# Power_Supply.net
KiCad netlist of a schematic drawn in Altium Designer
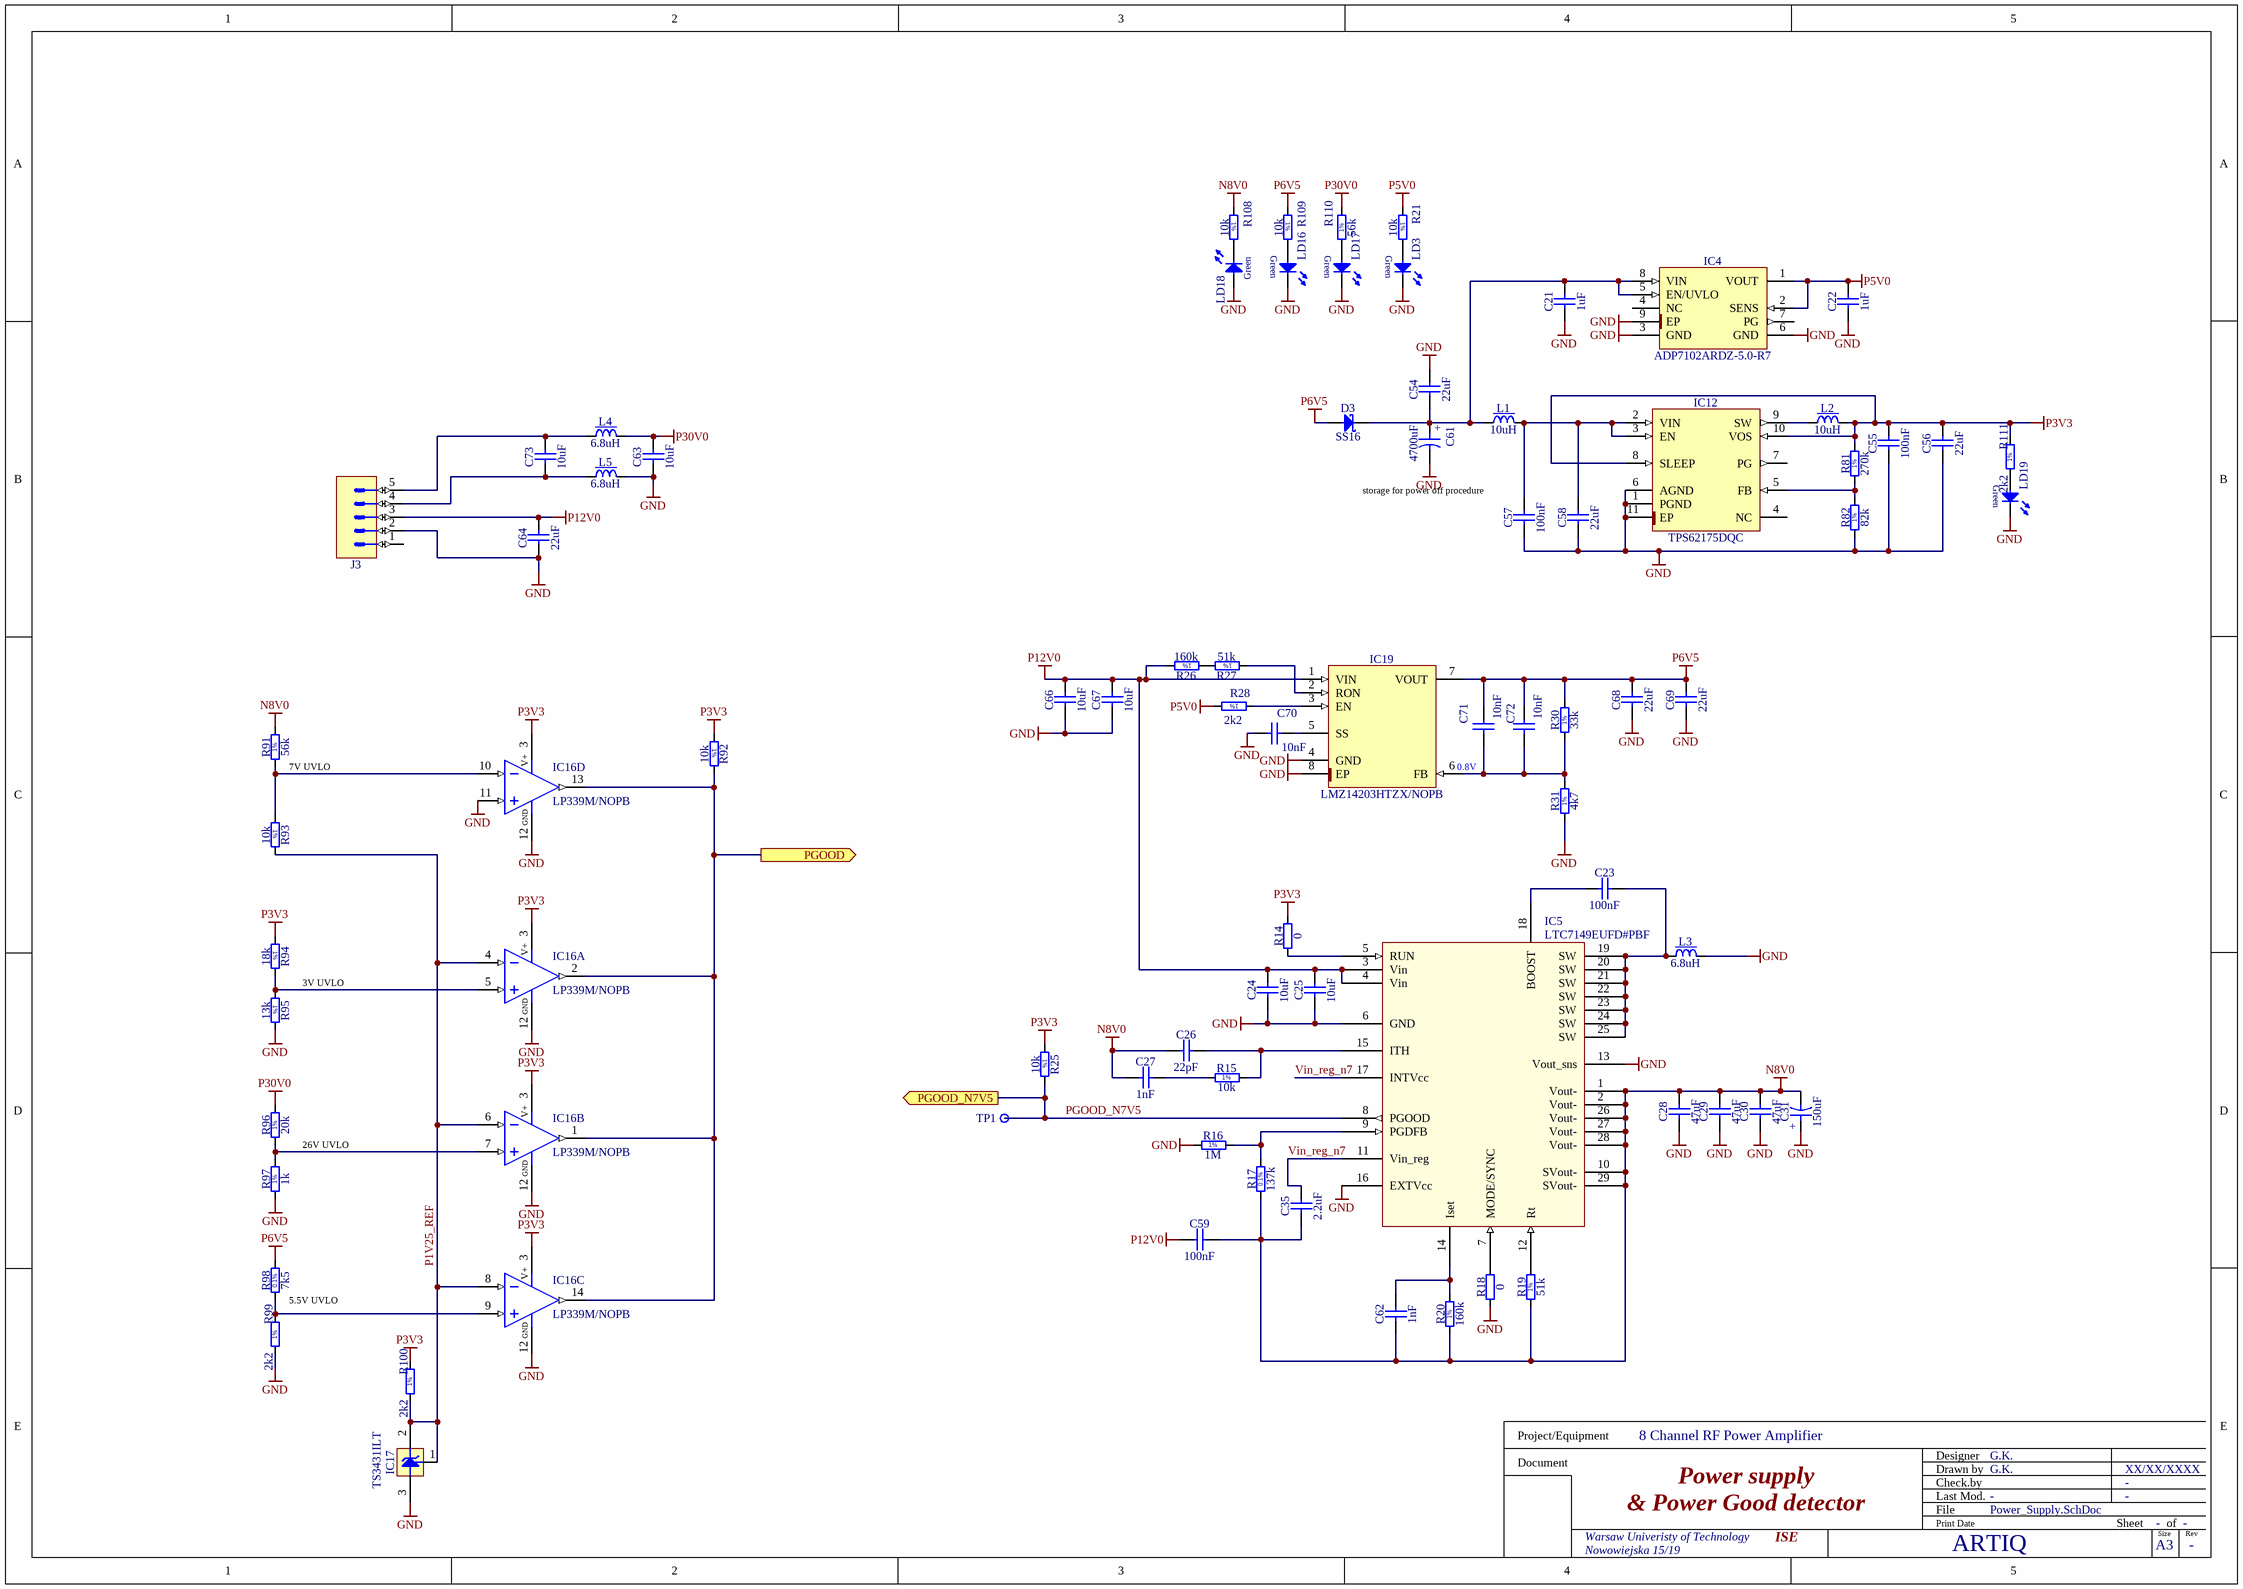
[diagram p0: Power_Supply.SchDoc]

(export (version "E")
  (design (tool "Eeschema 10.0.6"))
  (components
    (comp (ref "C21")
      (value "1uF")
      (footprint "CAPC2012X140N")
      (description "Non-polarised capacitor")
      (fields
        (field (name "PART NUMBER") "CC0805_1UF_35V_20%_X7R")
        (field (name "VOLTAGE") "35V")
        (field (name "AUTHOR") "CERN DEM JLC")
      )
      (libsource (lib "Capacitors") (part "Capacitor - non polarized"))
    )
    (comp (ref "C22")
      (value "1uF")
      (footprint "CAPC2012X140N")
      (description "Non-polarised capacitor")
      (fields
        (field (name "PART NUMBER") "CC0805_1UF_35V_20%_X7R")
        (field (name "VOLTAGE") "35V")
        (field (name "AUTHOR") "CERN DEM JLC")
      )
      (libsource (lib "Capacitors") (part "Capacitor - non polarized"))
    )
    (comp (ref "C23")
      (value "100nF")
      (footprint "CAPC1005X55N")
      (description "Non-polarised capacitor")
      (fields
        (field (name "PART NUMBER") "CC0402_100NF_16V_10%_X7R")
        (field (name "VOLTAGE") "16V")
        (field (name "AUTHOR") "CERN DEM JLC")
      )
      (libsource (lib "Capacitors") (part "Capacitor - non polarized"))
    )
    (comp (ref "C24")
      (value "10uF")
      (footprint "CAPC3216X190N")
      (description "Non-polarised capacitor")
      (fields
        (field (name "PART NUMBER") "CC1206_10UF_50V_10%_X5R_TDK_CGA5L3X5R1H106K160AB")
        (field (name "VOLTAGE") "50V")
        (field (name "AUTHOR") "CERN DEM BC")
      )
      (libsource (lib "Capacitors") (part "Capacitor - non polarized"))
    )
    (comp (ref "C25")
      (value "10uF")
      (footprint "CAPC3216X190N")
      (description "Non-polarised capacitor")
      (fields
        (field (name "PART NUMBER") "CC1206_10UF_50V_10%_X5R_TDK_CGA5L3X5R1H106K160AB")
        (field (name "VOLTAGE") "50V")
        (field (name "AUTHOR") "CERN DEM BC")
      )
      (libsource (lib "Capacitors") (part "Capacitor - non polarized"))
    )
    (comp (ref "C26")
      (value "22pF")
      (footprint "CAPC1005X55N")
      (description "Non-polarised capacitor")
      (fields
        (field (name "PART NUMBER") "CC0402_22PF_50V_5%_C0G")
        (field (name "VOLTAGE") "50V")
        (field (name "AUTHOR") "CERN DEM JLC")
      )
      (libsource (lib "Capacitors") (part "Capacitor - non polarized"))
    )
    (comp (ref "C27")
      (value "1nF")
      (footprint "CAPC1005X55N")
      (description "Non-polarised capacitor")
      (fields
        (field (name "PART NUMBER") "CC0402_1NF_50V_10%_X7R")
        (field (name "VOLTAGE") "50V")
        (field (name "AUTHOR") "CERN DEM JLC")
      )
      (libsource (lib "Capacitors") (part "Capacitor - non polarized"))
    )
    (comp (ref "C28")
      (value "47uF")
      (footprint "CAPC3216X180N")
      (description "Non-polarised capacitor")
      (fields
        (field (name "PART NUMBER") "CC1206_47UF_25V_20%_X5R")
        (field (name "VOLTAGE") "25V")
        (field (name "AUTHOR") "CERN DEM JLC")
      )
      (libsource (lib "Capacitors") (part "Capacitor - non polarized"))
    )
    (comp (ref "C29")
      (value "47uF")
      (footprint "CAPC3216X180N")
      (description "Non-polarised capacitor")
      (fields
        (field (name "PART NUMBER") "CC1206_47UF_25V_20%_X5R")
        (field (name "VOLTAGE") "25V")
        (field (name "AUTHOR") "CERN DEM JLC")
      )
      (libsource (lib "Capacitors") (part "Capacitor - non polarized"))
    )
    (comp (ref "C30")
      (value "47uF")
      (footprint "CAPC3216X180N")
      (description "Non-polarised capacitor")
      (fields
        (field (name "PART NUMBER") "CC1206_47UF_25V_20%_X5R")
        (field (name "VOLTAGE") "25V")
        (field (name "AUTHOR") "CERN DEM JLC")
      )
      (libsource (lib "Capacitors") (part "Capacitor - non polarized"))
    )
    (comp (ref "C31")
      (value "150uF")
      (footprint "CAPMP7343X310N")
      (description "Polarised capacitor")
      (fields
        (field (name "PART NUMBER") "CTE7343-31_150UF_16V_10%_LESR0100")
        (field (name "VOLTAGE") "16V")
        (field (name "AUTHOR") "CERN DEM JLC")
      )
      (libsource (lib "Capacitors") (part "Capacitor - polarized"))
    )
    (comp (ref "C35")
      (value "2.2uF")
      (footprint "CAPC1608X87N")
      (description "Non-polarised capacitor")
      (fields
        (field (name "PART NUMBER") "CC0603_2.2UF_16V_10%_X5R")
        (field (name "VOLTAGE") "16V")
        (field (name "AUTHOR") "CERN DEM JLC")
      )
      (libsource (lib "Capacitors") (part "Capacitor - non polarized"))
    )
    (comp (ref "C54")
      (value "22uF")
      (footprint "CAPC2012X135N")
      (description "Non-polarised capacitor")
      (fields
        (field (name "PART NUMBER") "CC0805_22UF_16V_10%_X5R")
        (field (name "VOLTAGE") "16V")
        (field (name "AUTHOR") "CERN DEM JLC")
      )
      (libsource (lib "Capacitors") (part "Capacitor - non polarized"))
    )
    (comp (ref "C55")
      (value "100nF")
      (footprint "CAPC1005X55N")
      (description "Non-polarised capacitor")
      (fields
        (field (name "PART NUMBER") "CC0402_100NF_16V_10%_X5R")
        (field (name "VOLTAGE") "16V")
        (field (name "AUTHOR") "CERN DEM JLC")
      )
      (libsource (lib "Capacitors") (part "Capacitor - non polarized"))
    )
    (comp (ref "C56")
      (value "22uF")
      (footprint "CAPC2012X135N")
      (description "Non-polarised capacitor")
      (fields
        (field (name "PART NUMBER") "CC0805_22UF_16V_10%_X5R")
        (field (name "VOLTAGE") "16V")
        (field (name "AUTHOR") "CERN DEM JLC")
      )
      (libsource (lib "Capacitors") (part "Capacitor - non polarized"))
    )
    (comp (ref "C57")
      (value "100nF")
      (footprint "CAPC1005X55N")
      (description "Non-polarised capacitor")
      (fields
        (field (name "PART NUMBER") "CC0402_100NF_16V_10%_X5R")
        (field (name "VOLTAGE") "16V")
        (field (name "AUTHOR") "CERN DEM JLC")
      )
      (libsource (lib "Capacitors") (part "Capacitor - non polarized"))
    )
    (comp (ref "C58")
      (value "22uF")
      (footprint "CAPC2012X135N")
      (description "Non-polarised capacitor")
      (fields
        (field (name "PART NUMBER") "CC0805_22UF_16V_10%_X5R")
        (field (name "VOLTAGE") "16V")
        (field (name "AUTHOR") "CERN DEM JLC")
      )
      (libsource (lib "Capacitors") (part "Capacitor - non polarized"))
    )
    (comp (ref "C59")
      (value "100nF")
      (footprint "CAPC1608X87N")
      (description "Non-polarised capacitor")
      (fields
        (field (name "PART NUMBER") "CC0603_100NF_50V_10%_X5R")
        (field (name "VOLTAGE") "50V")
        (field (name "AUTHOR") "CERN DEM MR")
      )
      (libsource (lib "Capacitors") (part "Capacitor - non polarized"))
    )
    (comp (ref "C61")
      (value "4700uF")
      (footprint "CAPAE1900X1680N")
      (description "Polarised capacitor")
      (fields
        (field (name "PART NUMBER") "CAE1900-1680_4700UF_16V_20%")
        (field (name "VOLTAGE") "16V")
        (field (name "AUTHOR") "CERN DEM JLC")
      )
      (libsource (lib "Capacitors") (part "Capacitor - polarized"))
    )
    (comp (ref "C62")
      (value "1nF")
      (footprint "CAPC1005X55N")
      (description "Non-polarised capacitor")
      (fields
        (field (name "PART NUMBER") "CC0402_1NF_50V_10%_X7R")
        (field (name "VOLTAGE") "50V")
        (field (name "AUTHOR") "CERN DEM JLC")
      )
      (libsource (lib "Capacitors") (part "Capacitor - non polarized"))
    )
    (comp (ref "C63")
      (value "10uF")
      (footprint "CAPC3216X190N")
      (description "Non-polarised capacitor")
      (fields
        (field (name "PART NUMBER") "CC1206_10UF_50V_10%_X5R_TDK_CGA5L3X5R1H106K160AB")
        (field (name "VOLTAGE") "50V")
        (field (name "AUTHOR") "CERN DEM BC")
      )
      (libsource (lib "Capacitors") (part "Capacitor - non polarized"))
    )
    (comp (ref "C64")
      (value "22uF")
      (footprint "CAPC2012X135N")
      (description "Non-polarised capacitor")
      (fields
        (field (name "PART NUMBER") "CC0805_22UF_16V_10%_X5R")
        (field (name "VOLTAGE") "16V")
        (field (name "AUTHOR") "CERN DEM JLC")
      )
      (libsource (lib "Capacitors") (part "Capacitor - non polarized"))
    )
    (comp (ref "C66")
      (value "10uF")
      (footprint "CAPC3216X190N")
      (description "Non-polarised capacitor")
      (fields
        (field (name "PART NUMBER") "CC1206_10UF_50V_10%_X5R_TDK_CGA5L3X5R1H106K160AB")
        (field (name "VOLTAGE") "50V")
        (field (name "AUTHOR") "CERN DEM BC")
      )
      (libsource (lib "Capacitors") (part "Capacitor - non polarized"))
    )
    (comp (ref "C67")
      (value "10uF")
      (footprint "CAPC3216X190N")
      (description "Non-polarised capacitor")
      (fields
        (field (name "PART NUMBER") "CC1206_10UF_50V_10%_X5R_TDK_CGA5L3X5R1H106K160AB")
        (field (name "VOLTAGE") "50V")
        (field (name "AUTHOR") "CERN DEM BC")
      )
      (libsource (lib "Capacitors") (part "Capacitor - non polarized"))
    )
    (comp (ref "C68")
      (value "22uF")
      (footprint "CAPC2012X135N")
      (description "Non-polarised capacitor")
      (fields
        (field (name "PART NUMBER") "CC0805_22UF_16V_10%_X5R")
        (field (name "VOLTAGE") "16V")
        (field (name "AUTHOR") "CERN DEM JLC")
      )
      (libsource (lib "Capacitors") (part "Capacitor - non polarized"))
    )
    (comp (ref "C69")
      (value "22uF")
      (footprint "CAPC2012X135N")
      (description "Non-polarised capacitor")
      (fields
        (field (name "PART NUMBER") "CC0805_22UF_16V_10%_X5R")
        (field (name "VOLTAGE") "16V")
        (field (name "AUTHOR") "CERN DEM JLC")
      )
      (libsource (lib "Capacitors") (part "Capacitor - non polarized"))
    )
    (comp (ref "C70")
      (value "10nF")
      (footprint "CAPC1608X87N")
      (description "Non-polarised capacitor")
      (fields
        (field (name "PART NUMBER") "CC0603_10NF_50V_5%_C0G")
        (field (name "VOLTAGE") "50V")
        (field (name "AUTHOR") "CERN DEM JLC")
      )
      (libsource (lib "Capacitors") (part "Capacitor - non polarized"))
    )
    (comp (ref "C71")
      (value "10nF")
      (footprint "CAPC1608X87N")
      (description "Non-polarised capacitor")
      (fields
        (field (name "PART NUMBER") "CC0603_10NF_50V_5%_C0G")
        (field (name "VOLTAGE") "50V")
        (field (name "AUTHOR") "CERN DEM JLC")
      )
      (libsource (lib "Capacitors") (part "Capacitor - non polarized"))
    )
    (comp (ref "C72")
      (value "10nF")
      (footprint "CAPC1608X87N")
      (description "Non-polarised capacitor")
      (fields
        (field (name "PART NUMBER") "CC0603_10NF_50V_5%_C0G")
        (field (name "VOLTAGE") "50V")
        (field (name "AUTHOR") "CERN DEM JLC")
      )
      (libsource (lib "Capacitors") (part "Capacitor - non polarized"))
    )
    (comp (ref "C73")
      (value "10uF")
      (footprint "CAPC3216X190N")
      (description "Non-polarised capacitor")
      (fields
        (field (name "PART NUMBER") "CC1206_10UF_50V_10%_X5R_TDK_CGA5L3X5R1H106K160AB")
        (field (name "VOLTAGE") "50V")
        (field (name "AUTHOR") "CERN DEM BC")
      )
      (libsource (lib "Capacitors") (part "Capacitor - non polarized"))
    )
    (comp (ref "D3")
      (value "SS16")
      (footprint "DIOM5127X229N")
      (description "Schottky Diode")
      (fields
        (field (name "VOLTAGE") "60V")
        (field (name "POWER") "1A")
        (field (name "AUTHOR") "CERN DEM JLC")
      )
      (libsource (lib "ICs And Semiconductors") (part "Diode Schottky"))
    )
    (comp (ref "IC4")
      (value "ADP7102ARDZ-5.0-R7")
      (footprint "SOIC127P600X175-9N-R241X309")
      (description "300 mA, Low Noise, CMOS LDO Linear Regulator")
      (fields (field (name "MANUFACTURER") "ANALOG DEVICES") (field (name "AUTHOR") "CERN DEM JLC"))
      (libsource (lib "ICs And Semiconductors") (part "ADP7102ARDZ-X.X-R7"))
    )
    (comp (ref "IC5")
      (value "LTC7149EUFD#PBF")
      (footprint "QFN50P400X500X80_HS-29N")
      (description "LTC7149 - 60V, 4A Synchronous Step-Down Regulator for Inverting Outputs")
      (fields (field (name "MANUFACTURER") "Linear technology"))
      (libsource (lib "misc") (part "LTC7149EUFD#PBF"))
    )
    (comp (ref "IC12")
      (value "TPS62175DQC")
      (footprint "SON50P200X300X80-11N-R94X250")
      (description "4.75-28VDC to 1-6VDC, 500mA Step-Down Converter With Sleep Mode")
      (fields (field (name "MANUFACTURER") "TEXAS INSTRUMENTS") (field (name "AUTHOR") "CERN DEM JMW"))
      (libsource (lib "ICs And Semiconductors") (part "TPS62175"))
    )
    (comp (ref "IC16")
      (value "LP339M/NOPB")
      (footprint "SOIC127P600X175-14N")
      (description "Quad Operational Amplifier")
      (fields (field (name "MANUFACTURER") "TEXAS INSTRUMENTS") (field (name "AUTHOR") "CERN DEM MR"))
      (libsource (lib "ICs And Semiconductors") (part "Operational Amplifier x4 Type5"))
    )
    (comp (ref "IC17")
      (value "TS3431ILT")
      (footprint "SOT95P237X112-3N")
      (description "Precision Reference 1=Adj 2=Cathode 3=Anode")
      (fields (field (name "MANUFACTURER") "ST MICROELECTRONICS") (field (name "AUTHOR") "CERN DEM JLC"))
      (libsource (lib "ICs And Semiconductors") (part "VREF 1ADJ-2C-3A"))
    )
    (comp (ref "IC19")
      (value "LMZ14203HTZX/NOPB")
      (footprint "TEXAS_TO-PMOD (NDW)")
      (description "3A SIMPLE SWITCHER® Power Module with 42V Maximum Input Voltage")
      (fields (field (name "MANUFACTURER") "TEXAS INSTRUMENTS") (field (name "AUTHOR") "GK"))
      (libsource (lib "LIBRARY_SCH") (part "PM_LMZ14203"))
    )
    (comp (ref "J3")
      (value "~")
      (footprint "PHOENIX_1755765")
      (description "Connector 5 Male")
      (fields
        (field (name "PART NUMBER") "PHOENIX_1755765")
        (field (name "MANUFACTURER") "PHOENIX CONTACT")
        (field (name "AUTHOR") "CERN DEM JLC")
      )
      (libsource (lib "Connectors") (part "Connector 5 Male"))
    )
    (comp (ref "L1")
      (value "10uH")
      (footprint "IND_MURATA-PS_8400")
      (description "Inductor With Core")
      (fields
        (field (name "PART NUMBER") "IND_10UH_10%_MURATA-PS_8400")
        (field (name "POWER") "950mA")
        (field (name "AUTHOR") "CERN DEM JLC")
      )
      (libsource (lib "Inductors & Transformers") (part "Inductor With Magnetic core"))
    )
    (comp (ref "L2")
      (value "10uH")
      (footprint "IND_MURATA-PS_8400")
      (description "Inductor With Core")
      (fields
        (field (name "PART NUMBER") "IND_10UH_10%_MURATA-PS_8400")
        (field (name "POWER") "950mA")
        (field (name "AUTHOR") "CERN DEM JLC")
      )
      (libsource (lib "Inductors & Transformers") (part "Inductor With Magnetic core"))
    )
    (comp (ref "L3")
      (value "6.8uH")
      (footprint "INDM6965X300N")
      (description "Inductor With Core")
      (fields
        (field (name "PART NUMBER") "IND2525_1.5UH_20%_VISHAY_IHLP-2525CZ")
        (field (name "POWER") "9A")
        (field (name "AUTHOR") "CERN DEM JLC")
      )
      (libsource (lib "Inductors & Transformers") (part "Inductor With Magnetic core"))
    )
    (comp (ref "L4")
      (value "6.8uH")
      (footprint "INDM6965X300N")
      (description "Inductor With Core")
      (fields
        (field (name "PART NUMBER") "IND2525_1.5UH_20%_VISHAY_IHLP-2525CZ")
        (field (name "POWER") "9A")
        (field (name "AUTHOR") "CERN DEM JLC")
      )
      (libsource (lib "Inductors & Transformers") (part "Inductor With Magnetic core"))
    )
    (comp (ref "L5")
      (value "6.8uH")
      (footprint "INDM6965X300N")
      (description "Inductor With Core")
      (fields
        (field (name "PART NUMBER") "IND2525_1.5UH_20%_VISHAY_IHLP-2525CZ")
        (field (name "POWER") "9A")
        (field (name "AUTHOR") "CERN DEM JLC")
      )
      (libsource (lib "Inductors & Transformers") (part "Inductor With Magnetic core"))
    )
    (comp (ref "LD3")
      (value "Green")
      (footprint "LED_KINGBRIGHT_KPH-1608CGCK")
      (description "LED Green 1C 2A")
      (fields
        (field (name "PART NUMBER") "LED_KINGBRIGHT_KPH-1608CGCK")
        (field (name "MANUFACTURER") "KINGBRIGHT")
        (field (name "AUTHOR") "CERN DEM JLC")
      )
      (libsource (lib "ICs And Semiconductors") (part "LED Green 1C 2A"))
    )
    (comp (ref "LD16")
      (value "Green")
      (footprint "LED_KINGBRIGHT_KPH-1608CGCK")
      (description "LED Green 1C 2A")
      (fields
        (field (name "PART NUMBER") "LED_KINGBRIGHT_KPH-1608CGCK")
        (field (name "MANUFACTURER") "KINGBRIGHT")
        (field (name "AUTHOR") "CERN DEM JLC")
      )
      (libsource (lib "ICs And Semiconductors") (part "LED Green 1C 2A"))
    )
    (comp (ref "LD17")
      (value "Green")
      (footprint "LED_KINGBRIGHT_KPH-1608CGCK")
      (description "LED Green 1C 2A")
      (fields
        (field (name "PART NUMBER") "LED_KINGBRIGHT_KPH-1608CGCK")
        (field (name "MANUFACTURER") "KINGBRIGHT")
        (field (name "AUTHOR") "CERN DEM JLC")
      )
      (libsource (lib "ICs And Semiconductors") (part "LED Green 1C 2A"))
    )
    (comp (ref "LD18")
      (value "Green")
      (footprint "LED_KINGBRIGHT_KPH-1608CGCK")
      (description "LED Green 1C 2A")
      (fields
        (field (name "PART NUMBER") "LED_KINGBRIGHT_KPH-1608CGCK")
        (field (name "MANUFACTURER") "KINGBRIGHT")
        (field (name "AUTHOR") "CERN DEM JLC")
      )
      (libsource (lib "ICs And Semiconductors") (part "LED Green 1C 2A"))
    )
    (comp (ref "LD19")
      (value "Green")
      (footprint "LED_OSRAM_LGL29K")
      (description "LED Green 1C 2A")
      (fields
        (field (name "PART NUMBER") "LED_OSRAM_LG L29K-G2J1-24-Z")
        (field (name "MANUFACTURER") "OSRAM")
        (field (name "AUTHOR") "CERN DEM JLC")
      )
      (libsource (lib "ICs And Semiconductors") (part "LED Green 1C 2A"))
    )
    (comp (ref "R14")
      (value "0")
      (footprint "RESC1005X40N")
      (description "Resistor")
      (fields
        (field (name "PART NUMBER") "R0402_0R_JUMPER")
        (field (name "MANUFACTURER") "GENERIC")
        (field (name "AUTHOR") "CERN DEM JLC")
      )
      (libsource (lib "Resistors") (part "Resistor"))
    )
    (comp (ref "R15")
      (value "10k")
      (footprint "RESC1005X40N")
      (description "Resistor - 1%")
      (fields
        (field (name "PART NUMBER") "R0402_10K_1%_0.0625W_100PPM")
        (field (name "POWER") "0.0625W")
        (field (name "AUTHOR") "CERN DEM JLC")
      )
      (libsource (lib "Resistors") (part "Resistor - 1%"))
    )
    (comp (ref "R16")
      (value "1M")
      (footprint "RESC1005X40N")
      (description "Resistor - 1%")
      (fields
        (field (name "PART NUMBER") "R0402_1M_1%_0.0625W_100PPM")
        (field (name "POWER") "0.0625W")
        (field (name "AUTHOR") "CERN DEM JLC")
      )
      (libsource (lib "Resistors") (part "Resistor - 1%"))
    )
    (comp (ref "R17")
      (value "137k")
      (footprint "RESC1608X55N")
      (description "Resistor - 0.1%")
      (fields
        (field (name "PART NUMBER") "R0603_137K_0.1%_0.063W_10PPM")
        (field (name "POWER") "0.063W")
        (field (name "AUTHOR") "CERN DEM JLC")
      )
      (libsource (lib "Resistors") (part "Resistor - 0.1%"))
    )
    (comp (ref "R18")
      (value "0")
      (footprint "RESC1005X40N")
      (description "Resistor")
      (fields
        (field (name "PART NUMBER") "R0402_0R_JUMPER")
        (field (name "MANUFACTURER") "GENERIC")
        (field (name "AUTHOR") "CERN DEM JLC")
      )
      (libsource (lib "Resistors") (part "Resistor"))
    )
    (comp (ref "R19")
      (value "51k")
      (footprint "RESC1005X40N")
      (description "Resistor - 1%")
      (fields
        (field (name "PART NUMBER") "R0402_51K_1%_0.0625W_100PPM")
        (field (name "POWER") "0.0625W")
        (field (name "AUTHOR") "CERN DEM JLC")
      )
      (libsource (lib "Resistors") (part "Resistor - 1%"))
    )
    (comp (ref "R20")
      (value "160k")
      (footprint "RESC1005X40N")
      (description "Resistor - 1%")
      (fields
        (field (name "PART NUMBER") "R0402_160K_1%_0.0625W_100PPM")
        (field (name "POWER") "0.0625W")
        (field (name "AUTHOR") "CERN DEM JLC")
      )
      (libsource (lib "Resistors") (part "Resistor - 1%"))
    )
    (comp (ref "R21")
      (value "10k")
      (footprint "RESC1005X40N")
      (description "Resistor - 1%")
      (fields
        (field (name "PART NUMBER") "R0402_10K_1%_0.0625W_100PPM")
        (field (name "POWER") "0.0625W")
        (field (name "AUTHOR") "CERN DEM JLC")
      )
      (libsource (lib "Resistors") (part "Resistor - 1%"))
    )
    (comp (ref "R25")
      (value "10k")
      (footprint "RESC1005X40N")
      (description "Resistor - 1%")
      (fields
        (field (name "PART NUMBER") "R0402_10K_1%_0.0625W_100PPM")
        (field (name "POWER") "0.0625W")
        (field (name "AUTHOR") "CERN DEM JLC")
      )
      (libsource (lib "Resistors") (part "Resistor - 1%"))
    )
    (comp (ref "R26")
      (value "160k")
      (footprint "RESC1005X40N")
      (description "Resistor - 1%")
      (fields
        (field (name "PART NUMBER") "R0402_160K_1%_0.0625W_100PPM")
        (field (name "POWER") "0.0625W")
        (field (name "AUTHOR") "CERN DEM JLC")
      )
      (libsource (lib "Resistors") (part "Resistor - 1%"))
    )
    (comp (ref "R27")
      (value "51k")
      (footprint "RESC1005X40N")
      (description "Resistor - 1%")
      (fields
        (field (name "PART NUMBER") "R0402_51K_1%_0.0625W_100PPM")
        (field (name "POWER") "0.0625W")
        (field (name "AUTHOR") "CERN DEM JLC")
      )
      (libsource (lib "Resistors") (part "Resistor - 1%"))
    )
    (comp (ref "R28")
      (value "2k2")
      (footprint "RESC1005X40N")
      (description "Resistor - 1%")
      (fields
        (field (name "PART NUMBER") "R0402_2K2_1%_0.0625W_100PPM")
        (field (name "POWER") "0.0625W")
        (field (name "AUTHOR") "CERN DEM JLC")
      )
      (libsource (lib "Resistors") (part "Resistor - 1%"))
    )
    (comp (ref "R30")
      (value "33k")
      (footprint "RESC1608X55N")
      (description "Resistor - 1%")
      (fields
        (field (name "PART NUMBER") "R0603_33K_1%_0.1W_100PPM")
        (field (name "POWER") "0.1W")
        (field (name "AUTHOR") "CERN DEM JLC")
      )
      (libsource (lib "Resistors") (part "Resistor - 1%"))
    )
    (comp (ref "R31")
      (value "4k7")
      (footprint "RESC1608X55N")
      (description "Resistor - 1%")
      (fields
        (field (name "PART NUMBER") "R0603_4K7_1%_0.1W_100PPM")
        (field (name "POWER") "0.1W")
        (field (name "AUTHOR") "CERN DEM JLC")
      )
      (libsource (lib "Resistors") (part "Resistor - 1%"))
    )
    (comp (ref "R81")
      (value "270k")
      (footprint "RESC1608X55N")
      (description "Resistor - 1%")
      (fields
        (field (name "PART NUMBER") "R0603_270K_1%_0.1W_100PPM")
        (field (name "POWER") "0.1W")
        (field (name "AUTHOR") "CERN DEM JLC")
      )
      (libsource (lib "Resistors") (part "Resistor - 1%"))
    )
    (comp (ref "R82")
      (value "82k")
      (footprint "RESC1608X55N")
      (description "Resistor - 1%")
      (fields
        (field (name "PART NUMBER") "R0603_82K_1%_0.1W_100PPM")
        (field (name "POWER") "0.1W")
        (field (name "AUTHOR") "CERN DEM JLC")
      )
      (libsource (lib "Resistors") (part "Resistor - 1%"))
    )
    (comp (ref "R91")
      (value "56k")
      (footprint "RESC1608X55N")
      (description "Resistor - 1%")
      (fields
        (field (name "PART NUMBER") "R0603_56K_1%_0.1W_100PPM")
        (field (name "POWER") "0.1W")
        (field (name "AUTHOR") "CERN DEM JLC")
      )
      (libsource (lib "Resistors") (part "Resistor - 1%"))
    )
    (comp (ref "R92")
      (value "10k")
      (footprint "RESC1005X40N")
      (description "Resistor - 1%")
      (fields
        (field (name "PART NUMBER") "R0402_10K_1%_0.0625W_100PPM")
        (field (name "POWER") "0.0625W")
        (field (name "AUTHOR") "CERN DEM JLC")
      )
      (libsource (lib "Resistors") (part "Resistor - 1%"))
    )
    (comp (ref "R93")
      (value "10k")
      (footprint "RESC1005X40N")
      (description "Resistor - 1%")
      (fields
        (field (name "PART NUMBER") "R0402_10K_1%_0.0625W_100PPM")
        (field (name "POWER") "0.0625W")
        (field (name "AUTHOR") "CERN DEM JLC")
      )
      (libsource (lib "Resistors") (part "Resistor - 1%"))
    )
    (comp (ref "R94")
      (value "18k")
      (footprint "RESC1608X55N")
      (description "Resistor - 1%")
      (fields
        (field (name "PART NUMBER") "R0603_18K_1%_0.1W_100PPM")
        (field (name "POWER") "0.1W")
        (field (name "AUTHOR") "CERN DEM JLC")
      )
      (libsource (lib "Resistors") (part "Resistor - 1%"))
    )
    (comp (ref "R95")
      (value "13k")
      (footprint "RESC1608X55N")
      (description "Resistor - 1%")
      (fields
        (field (name "PART NUMBER") "R0603_13K_1%_0.1W_100PPM")
        (field (name "POWER") "0.1W")
        (field (name "AUTHOR") "CERN DEM JLC")
      )
      (libsource (lib "Resistors") (part "Resistor - 1%"))
    )
    (comp (ref "R96")
      (value "20k")
      (footprint "RESC1608X55N")
      (description "Resistor - 1%")
      (fields
        (field (name "PART NUMBER") "R0603_20K_1%_0.1W_100PPM")
        (field (name "POWER") "0.1W")
        (field (name "AUTHOR") "CERN DEM JLC")
      )
      (libsource (lib "Resistors") (part "Resistor - 1%"))
    )
    (comp (ref "R97")
      (value "1k")
      (footprint "RESC1608X55N")
      (description "Resistor - 1%")
      (fields
        (field (name "PART NUMBER") "R0603_1K_1%_0.1W_100PPM")
        (field (name "POWER") "0.1W")
        (field (name "AUTHOR") "CERN DEM JLC")
      )
      (libsource (lib "Resistors") (part "Resistor - 1%"))
    )
    (comp (ref "R98")
      (value "7k5")
      (footprint "RESC1608X55N")
      (description "Resistor - 0.1%")
      (fields
        (field (name "PART NUMBER") "R0603_7K5_0.1%_0.063W_10PPM")
        (field (name "POWER") "0.063W")
        (field (name "AUTHOR") "CERN DEM JLC")
      )
      (libsource (lib "Resistors") (part "Resistor - 0.1%"))
    )
    (comp (ref "R99")
      (value "2k2")
      (footprint "RESC1005X40N")
      (description "Resistor - 1%")
      (fields
        (field (name "PART NUMBER") "R0402_2K2_1%_0.0625W_100PPM")
        (field (name "POWER") "0.0625W")
        (field (name "AUTHOR") "CERN DEM JLC")
      )
      (libsource (lib "Resistors") (part "Resistor - 1%"))
    )
    (comp (ref "R100")
      (value "2k2")
      (footprint "RESC1005X40N")
      (description "Resistor - 1%")
      (fields
        (field (name "PART NUMBER") "R0402_2K2_1%_0.0625W_100PPM")
        (field (name "POWER") "0.0625W")
        (field (name "AUTHOR") "CERN DEM JLC")
      )
      (libsource (lib "Resistors") (part "Resistor - 1%"))
    )
    (comp (ref "R108")
      (value "10k")
      (footprint "RESC1005X40N")
      (description "Resistor - 1%")
      (fields
        (field (name "PART NUMBER") "R0402_10K_1%_0.0625W_100PPM")
        (field (name "POWER") "0.0625W")
        (field (name "AUTHOR") "CERN DEM JLC")
      )
      (libsource (lib "Resistors") (part "Resistor - 1%"))
    )
    (comp (ref "R109")
      (value "10k")
      (footprint "RESC1005X40N")
      (description "Resistor - 1%")
      (fields
        (field (name "PART NUMBER") "R0402_10K_1%_0.0625W_100PPM")
        (field (name "POWER") "0.0625W")
        (field (name "AUTHOR") "CERN DEM JLC")
      )
      (libsource (lib "Resistors") (part "Resistor - 1%"))
    )
    (comp (ref "R110")
      (value "56k")
      (footprint "RESC1608X55N")
      (description "Resistor - 1%")
      (fields
        (field (name "PART NUMBER") "R0603_56K_1%_0.1W_100PPM")
        (field (name "POWER") "0.1W")
        (field (name "AUTHOR") "CERN DEM JLC")
      )
      (libsource (lib "Resistors") (part "Resistor - 1%"))
    )
    (comp (ref "R111")
      (value "2k2")
      (footprint "RESC1005X40N")
      (description "Resistor - 1%")
      (fields
        (field (name "PART NUMBER") "R0402_2K2_1%_0.0625W_100PPM")
        (field (name "POWER") "0.0625W")
        (field (name "AUTHOR") "CERN DEM JLC")
      )
      (libsource (lib "Resistors") (part "Resistor - 1%"))
    )
    (comp (ref "TP1")
      (value "Test Point")
      (footprint "TPS127")
      (fields (field (name "PART NUMBER") "SMD_PAD_1.27X1.27MM") (field (name "AUTHOR") "CERN DEM JLC"))
      (libsource (lib "Eletro-mechanical") (part "Test Point"))
    )
  )
  (nets
    (net (code "1") (name "/P1V25_REF") (class "Default")
      (node (ref "IC16") (pin "4") (pinfunction "IN-_4") (pintype "input"))
      (node (ref "IC16") (pin "6") (pinfunction "IN-_6") (pintype "input"))
      (node (ref "IC16") (pin "8") (pinfunction "IN-_8") (pintype "input"))
      (node (ref "IC17") (pin "1") (pinfunction "Adj_1") (pintype "passive"))
      (node (ref "IC17") (pin "2") (pinfunction "C_2") (pintype "passive"))
      (node (ref "R100") (pin "1") (pinfunction "1_1") (pintype "passive"))
      (node (ref "R93") (pin "2") (pinfunction "2_2") (pintype "passive"))
    )
    (net (code "2") (name "/PGOOD") (class "Default")
      (node (ref "IC16") (pin "1") (pinfunction "OUT_1") (pintype "output"))
      (node (ref "IC16") (pin "13") (pinfunction "OUT_13") (pintype "output"))
      (node (ref "IC16") (pin "14") (pinfunction "OUT_14") (pintype "output"))
      (node (ref "IC16") (pin "2") (pinfunction "OUT_2") (pintype "output"))
      (node (ref "R92") (pin "2") (pinfunction "2_2") (pintype "passive"))
    )
    (net (code "3") (name "/PGOOD_N7V5") (class "Default")
      (node (ref "IC5") (pin "8") (pinfunction "PGOOD_8") (pintype "output"))
      (node (ref "R25") (pin "2") (pinfunction "2_2") (pintype "passive"))
      (node (ref "TP1") (pin "1") (pinfunction "1_1") (pintype "bidirectional"))
    )
    (net (code "4") (name "/Vin_reg_n7") (class "Default")
      (node (ref "C35") (pin "2") (pinfunction "2_2") (pintype "passive"))
      (node (ref "IC5") (pin "11") (pinfunction "Vin_reg_11") (pintype "passive"))
      (node (ref "IC5") (pin "17") (pinfunction "INTVcc_17") (pintype "power_in"))
    )
    (net (code "5") (name "GND") (class "Default")
      (node (ref "C21") (pin "1") (pinfunction "1_1") (pintype "passive"))
      (node (ref "C22") (pin "1") (pinfunction "1_1") (pintype "passive"))
      (node (ref "C24") (pin "1") (pinfunction "1_1") (pintype "passive"))
      (node (ref "C25") (pin "1") (pinfunction "1_1") (pintype "passive"))
      (node (ref "C28") (pin "1") (pinfunction "1_1") (pintype "passive"))
      (node (ref "C29") (pin "1") (pinfunction "1_1") (pintype "passive"))
      (node (ref "C30") (pin "1") (pinfunction "1_1") (pintype "passive"))
      (node (ref "C31") (pin "1") (pinfunction "1_1") (pintype "passive"))
      (node (ref "C54") (pin "2") (pinfunction "2_2") (pintype "passive"))
      (node (ref "C55") (pin "1") (pinfunction "1_1") (pintype "passive"))
      (node (ref "C56") (pin "1") (pinfunction "1_1") (pintype "passive"))
      (node (ref "C57") (pin "1") (pinfunction "1_1") (pintype "passive"))
      (node (ref "C58") (pin "1") (pinfunction "1_1") (pintype "passive"))
      (node (ref "C61") (pin "2") (pinfunction "2_2") (pintype "passive"))
      (node (ref "C63") (pin "1") (pinfunction "1_1") (pintype "passive"))
      (node (ref "C64") (pin "1") (pinfunction "1_1") (pintype "passive"))
      (node (ref "C66") (pin "1") (pinfunction "1_1") (pintype "passive"))
      (node (ref "C67") (pin "1") (pinfunction "1_1") (pintype "passive"))
      (node (ref "C68") (pin "1") (pinfunction "1_1") (pintype "passive"))
      (node (ref "C69") (pin "1") (pinfunction "1_1") (pintype "passive"))
      (node (ref "C70") (pin "1") (pinfunction "1_1") (pintype "passive"))
      (node (ref "IC12") (pin "1") (pinfunction "PGND_1") (pintype "power_in"))
      (node (ref "IC12") (pin "11") (pinfunction "EP_11") (pintype "power_in"))
      (node (ref "IC12") (pin "6") (pinfunction "AGND_6") (pintype "power_in"))
      (node (ref "IC16") (pin "11") (pinfunction "IN+_11") (pintype "input"))
      (node (ref "IC16") (pin "12") (pinfunction "GND_12") (pintype "power_in"))
      (node (ref "IC17") (pin "3") (pinfunction "A_3") (pintype "passive"))
      (node (ref "IC19") (pin "4") (pinfunction "GND_4") (pintype "power_in"))
      (node (ref "IC19") (pin "8") (pinfunction "EP_8") (pintype "power_in"))
      (node (ref "IC4") (pin "3") (pinfunction "GND_3") (pintype "power_in"))
      (node (ref "IC4") (pin "6") (pinfunction "GND_6") (pintype "power_in"))
      (node (ref "IC4") (pin "9") (pinfunction "EP_9") (pintype "power_in"))
      (node (ref "IC5") (pin "13") (pinfunction "Vout_sns_13") (pintype "passive"))
      (node (ref "IC5") (pin "16") (pinfunction "EXTVcc_16") (pintype "power_in"))
      (node (ref "IC5") (pin "6") (pinfunction "GND_6") (pintype "power_in"))
      (node (ref "J3") (pin "2") (pinfunction "2_2") (pintype "bidirectional"))
      (node (ref "L3") (pin "2") (pinfunction "2_2") (pintype "passive"))
      (node (ref "L5") (pin "2") (pinfunction "2_2") (pintype "passive"))
      (node (ref "LD16") (pin "1") (pinfunction "C_1") (pintype "passive"))
      (node (ref "LD17") (pin "1") (pinfunction "C_1") (pintype "passive"))
      (node (ref "LD18") (pin "2") (pinfunction "A_2") (pintype "passive"))
      (node (ref "LD19") (pin "1") (pinfunction "C_1") (pintype "passive"))
      (node (ref "LD3") (pin "1") (pinfunction "C_1") (pintype "passive"))
      (node (ref "R16") (pin "1") (pinfunction "1_1") (pintype "passive"))
      (node (ref "R18") (pin "1") (pinfunction "1_1") (pintype "passive"))
      (node (ref "R31") (pin "1") (pinfunction "1_1") (pintype "passive"))
      (node (ref "R82") (pin "1") (pinfunction "1_1") (pintype "passive"))
      (node (ref "R95") (pin "2") (pinfunction "2_2") (pintype "passive"))
      (node (ref "R97") (pin "1") (pinfunction "1_1") (pintype "passive"))
      (node (ref "R99") (pin "1") (pinfunction "1_1") (pintype "passive"))
    )
    (net (code "6") (name "N8V0") (class "Default")
      (node (ref "C26") (pin "1") (pinfunction "1_1") (pintype "passive"))
      (node (ref "C27") (pin "1") (pinfunction "1_1") (pintype "passive"))
      (node (ref "C28") (pin "2") (pinfunction "2_2") (pintype "passive"))
      (node (ref "C29") (pin "2") (pinfunction "2_2") (pintype "passive"))
      (node (ref "C30") (pin "2") (pinfunction "2_2") (pintype "passive"))
      (node (ref "C31") (pin "2") (pinfunction "2_2") (pintype "passive"))
      (node (ref "C35") (pin "1") (pinfunction "1_1") (pintype "passive"))
      (node (ref "C59") (pin "2") (pinfunction "2_2") (pintype "passive"))
      (node (ref "C62") (pin "1") (pinfunction "1_1") (pintype "passive"))
      (node (ref "IC5") (pin "1") (pinfunction "Vout-_1") (pintype "power_in"))
      (node (ref "IC5") (pin "10") (pinfunction "SVout-_10") (pintype "power_in"))
      (node (ref "IC5") (pin "2") (pinfunction "Vout-_2") (pintype "power_in"))
      (node (ref "IC5") (pin "26") (pinfunction "Vout-_26") (pintype "power_in"))
      (node (ref "IC5") (pin "27") (pinfunction "Vout-_27") (pintype "power_in"))
      (node (ref "IC5") (pin "28") (pinfunction "Vout-_28") (pintype "power_in"))
      (node (ref "IC5") (pin "29") (pinfunction "SVout-_29") (pintype "power_in"))
      (node (ref "R108") (pin "1") (pinfunction "1_1") (pintype "passive"))
      (node (ref "R17") (pin "1") (pinfunction "1_1") (pintype "passive"))
      (node (ref "R19") (pin "1") (pinfunction "1_1") (pintype "passive"))
      (node (ref "R20") (pin "1") (pinfunction "1_1") (pintype "passive"))
      (node (ref "R91") (pin "2") (pinfunction "2_2") (pintype "passive"))
    )
    (net (code "7") (name "Net-(C23-Pad2)") (class "Default")
      (node (ref "C23") (pin "2") (pinfunction "2_2") (pintype "passive"))
      (node (ref "IC5") (pin "19") (pinfunction "SW_19") (pintype "power_in"))
      (node (ref "IC5") (pin "20") (pinfunction "SW_20") (pintype "power_in"))
      (node (ref "IC5") (pin "21") (pinfunction "SW_21") (pintype "power_in"))
      (node (ref "IC5") (pin "22") (pinfunction "SW_22") (pintype "power_in"))
      (node (ref "IC5") (pin "23") (pinfunction "SW_23") (pintype "power_in"))
      (node (ref "IC5") (pin "24") (pinfunction "SW_24") (pintype "power_in"))
      (node (ref "IC5") (pin "25") (pinfunction "SW_25") (pintype "power_in"))
      (node (ref "L3") (pin "1") (pinfunction "1_1") (pintype "passive"))
    )
    (net (code "8") (name "Net-(C27-Pad2)") (class "Default")
      (node (ref "C27") (pin "2") (pinfunction "2_2") (pintype "passive"))
      (node (ref "R15") (pin "1") (pinfunction "1_1") (pintype "passive"))
    )
    (net (code "9") (name "Net-(C73-Pad1)") (class "Default")
      (node (ref "C73") (pin "1") (pinfunction "1_1") (pintype "passive"))
      (node (ref "J3") (pin "4") (pinfunction "4_4") (pintype "bidirectional"))
      (node (ref "L5") (pin "1") (pinfunction "1_1") (pintype "passive"))
    )
    (net (code "10") (name "Net-(C73-Pad2)") (class "Default")
      (node (ref "C73") (pin "2") (pinfunction "2_2") (pintype "passive"))
      (node (ref "J3") (pin "5") (pinfunction "5_5") (pintype "bidirectional"))
      (node (ref "L4") (pin "1") (pinfunction "1_1") (pintype "passive"))
    )
    (net (code "11") (name "Net-(D3-C)") (class "Default")
      (node (ref "C21") (pin "2") (pinfunction "2_2") (pintype "passive"))
      (node (ref "C54") (pin "1") (pinfunction "1_1") (pintype "passive"))
      (node (ref "C61") (pin "1") (pinfunction "1_1") (pintype "passive"))
      (node (ref "D3") (pin "1") (pinfunction "C_1") (pintype "passive"))
      (node (ref "IC4") (pin "5") (pinfunction "EN/UVLO_5") (pintype "input"))
      (node (ref "IC4") (pin "8") (pinfunction "VIN_8") (pintype "input"))
      (node (ref "L1") (pin "1") (pinfunction "1_1") (pintype "passive"))
    )
    (net (code "12") (name "Net-(IC5-BOOST)") (class "Default")
      (node (ref "C23") (pin "1") (pinfunction "1_1") (pintype "passive"))
      (node (ref "IC5") (pin "18") (pinfunction "BOOST_18") (pintype "passive"))
    )
    (net (code "13") (name "Net-(IC5-ITH)") (class "Default")
      (node (ref "C26") (pin "2") (pinfunction "2_2") (pintype "passive"))
      (node (ref "IC5") (pin "15") (pinfunction "ITH_15") (pintype "passive"))
      (node (ref "R15") (pin "2") (pinfunction "2_2") (pintype "passive"))
    )
    (net (code "14") (name "Net-(IC5-Iset)") (class "Default")
      (node (ref "C62") (pin "2") (pinfunction "2_2") (pintype "passive"))
      (node (ref "IC5") (pin "14") (pinfunction "Iset_14") (pintype "passive"))
      (node (ref "R20") (pin "2") (pinfunction "2_2") (pintype "passive"))
    )
    (net (code "15") (name "Net-(IC5-MODE{slash}SYNC)") (class "Default")
      (node (ref "IC5") (pin "7") (pinfunction "MODE/SYNC_7") (pintype "input"))
      (node (ref "R18") (pin "2") (pinfunction "2_2") (pintype "passive"))
    )
    (net (code "16") (name "Net-(IC5-PGDFB)") (class "Default")
      (node (ref "IC5") (pin "9") (pinfunction "PGDFB_9") (pintype "input"))
      (node (ref "R16") (pin "2") (pinfunction "2_2") (pintype "passive"))
      (node (ref "R17") (pin "2") (pinfunction "2_2") (pintype "passive"))
    )
    (net (code "17") (name "Net-(IC5-RUN)") (class "Default")
      (node (ref "IC5") (pin "5") (pinfunction "RUN_5") (pintype "input"))
      (node (ref "R14") (pin "1") (pinfunction "1_1") (pintype "passive"))
    )
    (net (code "18") (name "Net-(IC5-Rt)") (class "Default")
      (node (ref "IC5") (pin "12") (pinfunction "Rt_12") (pintype "input"))
      (node (ref "R19") (pin "2") (pinfunction "2_2") (pintype "passive"))
    )
    (net (code "19") (name "Net-(IC12-EN)") (class "Default")
      (node (ref "C57") (pin "2") (pinfunction "2_2") (pintype "passive"))
      (node (ref "C58") (pin "2") (pinfunction "2_2") (pintype "passive"))
      (node (ref "IC12") (pin "2") (pinfunction "VIN_2") (pintype "input"))
      (node (ref "IC12") (pin "3") (pinfunction "EN_3") (pintype "input"))
      (node (ref "L1") (pin "2") (pinfunction "2_2") (pintype "passive"))
    )
    (net (code "20") (name "Net-(IC12-FB)") (class "Default")
      (node (ref "IC12") (pin "5") (pinfunction "FB_5") (pintype "input"))
      (node (ref "R81") (pin "1") (pinfunction "1_1") (pintype "passive"))
      (node (ref "R82") (pin "2") (pinfunction "2_2") (pintype "passive"))
    )
    (net (code "21") (name "Net-(IC12-SW)") (class "Default")
      (node (ref "IC12") (pin "9") (pinfunction "SW_9") (pintype "output"))
      (node (ref "L2") (pin "1") (pinfunction "1_1") (pintype "passive"))
    )
    (net (code "22") (name "Net-(IC16A-IN+)") (class "Default")
      (node (ref "IC16") (pin "5") (pinfunction "IN+_5") (pintype "input"))
      (node (ref "R94") (pin "2") (pinfunction "2_2") (pintype "passive"))
      (node (ref "R95") (pin "1") (pinfunction "1_1") (pintype "passive"))
    )
    (net (code "23") (name "Net-(IC16B-IN+)") (class "Default")
      (node (ref "IC16") (pin "7") (pinfunction "IN+_7") (pintype "input"))
      (node (ref "R96") (pin "1") (pinfunction "1_1") (pintype "passive"))
      (node (ref "R97") (pin "2") (pinfunction "2_2") (pintype "passive"))
    )
    (net (code "24") (name "Net-(IC16C-IN+)") (class "Default")
      (node (ref "IC16") (pin "9") (pinfunction "IN+_9") (pintype "input"))
      (node (ref "R98") (pin "1") (pinfunction "1_1") (pintype "passive"))
      (node (ref "R99") (pin "2") (pinfunction "2_2") (pintype "passive"))
    )
    (net (code "25") (name "Net-(IC16D-IN-)") (class "Default")
      (node (ref "IC16") (pin "10") (pinfunction "IN-_10") (pintype "input"))
      (node (ref "R91") (pin "1") (pinfunction "1_1") (pintype "passive"))
      (node (ref "R93") (pin "1") (pinfunction "1_1") (pintype "passive"))
    )
    (net (code "26") (name "Net-(IC19-EN)") (class "Default")
      (node (ref "IC19") (pin "3") (pinfunction "EN_3") (pintype "input"))
      (node (ref "R28") (pin "1") (pinfunction "1_1") (pintype "passive"))
    )
    (net (code "27") (name "Net-(IC19-FB)") (class "Default")
      (node (ref "C71") (pin "1") (pinfunction "1_1") (pintype "passive"))
      (node (ref "C72") (pin "1") (pinfunction "1_1") (pintype "passive"))
      (node (ref "IC19") (pin "6") (pinfunction "FB_6") (pintype "input"))
      (node (ref "R30") (pin "1") (pinfunction "1_1") (pintype "passive"))
      (node (ref "R31") (pin "2") (pinfunction "2_2") (pintype "passive"))
    )
    (net (code "28") (name "Net-(IC19-RON)") (class "Default")
      (node (ref "IC19") (pin "2") (pinfunction "RON_2") (pintype "input"))
      (node (ref "R27") (pin "1") (pinfunction "1_1") (pintype "passive"))
    )
    (net (code "29") (name "Net-(IC19-SS)") (class "Default")
      (node (ref "C70") (pin "2") (pinfunction "2_2") (pintype "passive"))
      (node (ref "IC19") (pin "5") (pinfunction "SS_5") (pintype "passive"))
    )
    (net (code "30") (name "Net-(LD3-A)") (class "Default")
      (node (ref "LD3") (pin "2") (pinfunction "A_2") (pintype "passive"))
      (node (ref "R21") (pin "2") (pinfunction "2_2") (pintype "passive"))
    )
    (net (code "31") (name "Net-(LD16-A)") (class "Default")
      (node (ref "LD16") (pin "2") (pinfunction "A_2") (pintype "passive"))
      (node (ref "R109") (pin "2") (pinfunction "2_2") (pintype "passive"))
    )
    (net (code "32") (name "Net-(LD17-A)") (class "Default")
      (node (ref "LD17") (pin "2") (pinfunction "A_2") (pintype "passive"))
      (node (ref "R110") (pin "1") (pinfunction "1_1") (pintype "passive"))
    )
    (net (code "33") (name "Net-(LD18-C)") (class "Default")
      (node (ref "LD18") (pin "1") (pinfunction "C_1") (pintype "passive"))
      (node (ref "R108") (pin "2") (pinfunction "2_2") (pintype "passive"))
    )
    (net (code "34") (name "Net-(LD19-A)") (class "Default")
      (node (ref "LD19") (pin "2") (pinfunction "A_2") (pintype "passive"))
      (node (ref "R111") (pin "1") (pinfunction "1_1") (pintype "passive"))
    )
    (net (code "35") (name "Net-(R26-Pad1)") (class "Default")
      (node (ref "R26") (pin "1") (pinfunction "1_1") (pintype "passive"))
      (node (ref "R27") (pin "2") (pinfunction "2_2") (pintype "passive"))
    )
    (net (code "36") (name "P3V3") (class "Default")
      (node (ref "C55") (pin "2") (pinfunction "2_2") (pintype "passive"))
      (node (ref "C56") (pin "2") (pinfunction "2_2") (pintype "passive"))
      (node (ref "IC12") (pin "10") (pinfunction "VOS_10") (pintype "input"))
      (node (ref "IC12") (pin "8") (pinfunction "SLEEP_8") (pintype "input"))
      (node (ref "IC16") (pin "3") (pinfunction "V+_3") (pintype "power_in"))
      (node (ref "L2") (pin "2") (pinfunction "2_2") (pintype "passive"))
      (node (ref "R100") (pin "2") (pinfunction "2_2") (pintype "passive"))
      (node (ref "R111") (pin "2") (pinfunction "2_2") (pintype "passive"))
      (node (ref "R14") (pin "2") (pinfunction "2_2") (pintype "passive"))
      (node (ref "R25") (pin "1") (pinfunction "1_1") (pintype "passive"))
      (node (ref "R81") (pin "2") (pinfunction "2_2") (pintype "passive"))
      (node (ref "R92") (pin "1") (pinfunction "1_1") (pintype "passive"))
      (node (ref "R94") (pin "1") (pinfunction "1_1") (pintype "passive"))
    )
    (net (code "37") (name "P5V0") (class "Default")
      (node (ref "C22") (pin "2") (pinfunction "2_2") (pintype "passive"))
      (node (ref "IC4") (pin "1") (pinfunction "VOUT_1") (pintype "power_in"))
      (node (ref "IC4") (pin "2") (pinfunction "SENS_2") (pintype "input"))
      (node (ref "R21") (pin "1") (pinfunction "1_1") (pintype "passive"))
      (node (ref "R28") (pin "2") (pinfunction "2_2") (pintype "passive"))
    )
    (net (code "38") (name "P6V5") (class "Default")
      (node (ref "C68") (pin "2") (pinfunction "2_2") (pintype "passive"))
      (node (ref "C69") (pin "2") (pinfunction "2_2") (pintype "passive"))
      (node (ref "C71") (pin "2") (pinfunction "2_2") (pintype "passive"))
      (node (ref "C72") (pin "2") (pinfunction "2_2") (pintype "passive"))
      (node (ref "D3") (pin "2") (pinfunction "A_2") (pintype "passive"))
      (node (ref "IC19") (pin "7") (pinfunction "VOUT_7") (pintype "power_in"))
      (node (ref "R109") (pin "1") (pinfunction "1_1") (pintype "passive"))
      (node (ref "R30") (pin "2") (pinfunction "2_2") (pintype "passive"))
      (node (ref "R98") (pin "2") (pinfunction "2_2") (pintype "passive"))
    )
    (net (code "39") (name "P12V0") (class "Default")
      (node (ref "C24") (pin "2") (pinfunction "2_2") (pintype "passive"))
      (node (ref "C25") (pin "2") (pinfunction "2_2") (pintype "passive"))
      (node (ref "C59") (pin "1") (pinfunction "1_1") (pintype "passive"))
      (node (ref "C64") (pin "2") (pinfunction "2_2") (pintype "passive"))
      (node (ref "C66") (pin "2") (pinfunction "2_2") (pintype "passive"))
      (node (ref "C67") (pin "2") (pinfunction "2_2") (pintype "passive"))
      (node (ref "IC19") (pin "1") (pinfunction "VIN_1") (pintype "input"))
      (node (ref "IC5") (pin "3") (pinfunction "Vin_3") (pintype "power_in"))
      (node (ref "IC5") (pin "4") (pinfunction "Vin_4") (pintype "power_in"))
      (node (ref "J3") (pin "3") (pinfunction "3_3") (pintype "bidirectional"))
      (node (ref "R26") (pin "2") (pinfunction "2_2") (pintype "passive"))
    )
    (net (code "40") (name "P30V0") (class "Default")
      (node (ref "C63") (pin "2") (pinfunction "2_2") (pintype "passive"))
      (node (ref "L4") (pin "2") (pinfunction "2_2") (pintype "passive"))
      (node (ref "R110") (pin "2") (pinfunction "2_2") (pintype "passive"))
      (node (ref "R96") (pin "2") (pinfunction "2_2") (pintype "passive"))
    )
    (net (code "41") (name "unconnected-(IC4-NC-Pad4)") (class "Default")
      (node (ref "IC4") (pin "4") (pinfunction "NC_4") (pintype "passive"))
    )
    (net (code "42") (name "unconnected-(IC4-PG-Pad7)") (class "Default")
      (node (ref "IC4") (pin "7") (pinfunction "PG_7") (pintype "output"))
    )
    (net (code "43") (name "unconnected-(IC12-NC-Pad4)") (class "Default")
      (node (ref "IC12") (pin "4") (pinfunction "NC_4") (pintype "passive"))
    )
    (net (code "44") (name "unconnected-(IC12-PG-Pad7)") (class "Default")
      (node (ref "IC12") (pin "7") (pinfunction "PG_7") (pintype "output"))
    )
    (net (code "45") (name "unconnected-(J3-Pad1)") (class "Default")
      (node (ref "J3") (pin "1") (pinfunction "1_1") (pintype "bidirectional"))
    )
  )
)
